# SWD.net
KiCad netlist of a schematic drawn in Altium Designer
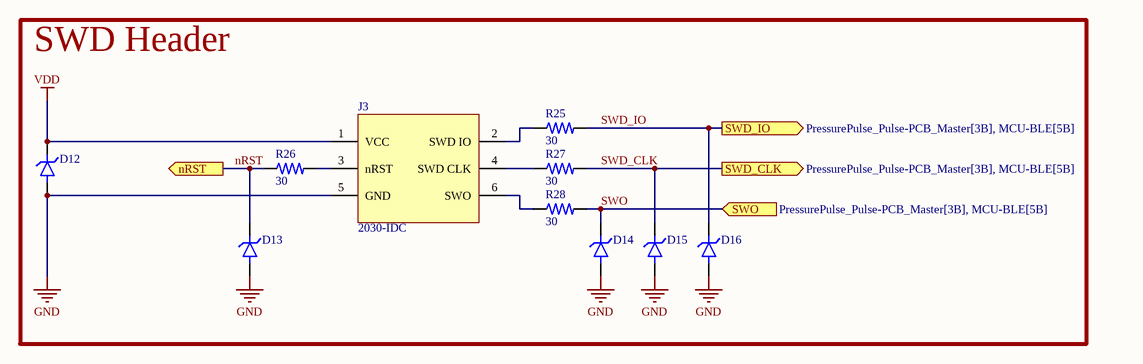
[diagram p0: SWD.SchDoc]

(export (version "E")
  (design (tool "Eeschema 10.0.6"))
  (components
    (comp (ref "D12")
      (value "RCLAMP0521P.TCT")
      (footprint "PressurePulse:BDFN2C051V40")
      (description "25V Clamp 4A (8/20µs) Ipp Tvs Diode Surface Mount SLP1006P2")
      (fields (field (name "MFR") "BORN"))
      (libsource (lib "PressurePulse") (part "TVS DIODE"))
    )
    (comp (ref "D13")
      (value "RCLAMP0521P.TCT")
      (footprint "PressurePulse:BDFN2C051V40")
      (description "25V Clamp 4A (8/20µs) Ipp Tvs Diode Surface Mount SLP1006P2")
      (fields (field (name "MFR") "BORN"))
      (libsource (lib "PressurePulse") (part "TVS DIODE"))
    )
    (comp (ref "D14")
      (value "RCLAMP0521P.TCT")
      (footprint "PressurePulse:BDFN2C051V40")
      (description "25V Clamp 4A (8/20µs) Ipp Tvs Diode Surface Mount SLP1006P2")
      (fields (field (name "MFR") "BORN"))
      (libsource (lib "PressurePulse") (part "TVS DIODE"))
    )
    (comp (ref "D15")
      (value "RCLAMP0521P.TCT")
      (footprint "PressurePulse:BDFN2C051V40")
      (description "25V Clamp 4A (8/20µs) Ipp Tvs Diode Surface Mount SLP1006P2")
      (fields (field (name "MFR") "BORN"))
      (libsource (lib "PressurePulse") (part "TVS DIODE"))
    )
    (comp (ref "D16")
      (value "RCLAMP0521P.TCT")
      (footprint "PressurePulse:BDFN2C051V40")
      (description "25V Clamp 4A (8/20µs) Ipp Tvs Diode Surface Mount SLP1006P2")
      (fields (field (name "MFR") "BORN"))
      (libsource (lib "PressurePulse") (part "TVS DIODE"))
    )
    (comp (ref "J3")
      (value "2030-IDC")
      (footprint "PressurePulse:TAG CONNECT TC2030IDC - NO 3D MODEL")
      (description "TAG CONNECT 2030-IDC")
      (fields (field (name "MFR") "Tag Connect"))
      (libsource (lib "PressurePulse") (part "TAG CONNECT 2030-IDC"))
    )
    (comp (ref "R25")
      (value "30")
      (footprint "PressurePulse:0402R")
      (description "Resistor")
      (fields (field (name "Comment") "RES"))
      (libsource (lib "PressurePulse") (part "RES"))
    )
    (comp (ref "R26")
      (value "30")
      (footprint "PressurePulse:0402R")
      (description "Resistor")
      (fields (field (name "Comment") "RES"))
      (libsource (lib "PressurePulse") (part "RES"))
    )
    (comp (ref "R27")
      (value "30")
      (footprint "PressurePulse:0402R")
      (description "Resistor")
      (fields (field (name "Comment") "RES"))
      (libsource (lib "PressurePulse") (part "RES"))
    )
    (comp (ref "R28")
      (value "30")
      (footprint "PressurePulse:0402R")
      (description "Resistor")
      (fields (field (name "Comment") "RES"))
      (libsource (lib "PressurePulse") (part "RES"))
    )
  )
  (nets
    (net (code "1") (name "/SWD_CLK") (class "Default")
      (node (ref "D15") (pin "K") (pinfunction "K_K") (pintype "passive"))
      (node (ref "R27") (pin "2") (pinfunction "2_2") (pintype "passive"))
    )
    (net (code "2") (name "/SWD_IO") (class "Default")
      (node (ref "D16") (pin "K") (pinfunction "K_K") (pintype "passive"))
      (node (ref "R25") (pin "2") (pinfunction "2_2") (pintype "passive"))
    )
    (net (code "3") (name "/SWO") (class "Default")
      (node (ref "D14") (pin "K") (pinfunction "K_K") (pintype "passive"))
      (node (ref "R28") (pin "2") (pinfunction "2_2") (pintype "passive"))
    )
    (net (code "4") (name "/nRST") (class "Default")
      (node (ref "D13") (pin "K") (pinfunction "K_K") (pintype "passive"))
      (node (ref "R26") (pin "1") (pinfunction "1_1") (pintype "passive"))
    )
    (net (code "5") (name "GND") (class "Default")
      (node (ref "D12") (pin "A") (pinfunction "A_A") (pintype "passive"))
      (node (ref "D13") (pin "A") (pinfunction "A_A") (pintype "passive"))
      (node (ref "D14") (pin "A") (pinfunction "A_A") (pintype "passive"))
      (node (ref "D15") (pin "A") (pinfunction "A_A") (pintype "passive"))
      (node (ref "D16") (pin "A") (pinfunction "A_A") (pintype "passive"))
      (node (ref "J3") (pin "5") (pinfunction "GND_5") (pintype "passive"))
    )
    (net (code "6") (name "Net-(J3-SWD_CLK)") (class "Default")
      (node (ref "J3") (pin "4") (pinfunction "SWD_CLK_4") (pintype "passive"))
      (node (ref "R27") (pin "1") (pinfunction "1_1") (pintype "passive"))
    )
    (net (code "7") (name "Net-(J3-SWD_IO)") (class "Default")
      (node (ref "J3") (pin "2") (pinfunction "SWD_IO_2") (pintype "passive"))
      (node (ref "R25") (pin "1") (pinfunction "1_1") (pintype "passive"))
    )
    (net (code "8") (name "Net-(J3-SWO)") (class "Default")
      (node (ref "J3") (pin "6") (pinfunction "SWO_6") (pintype "passive"))
      (node (ref "R28") (pin "1") (pinfunction "1_1") (pintype "passive"))
    )
    (net (code "9") (name "Net-(J3-nRST)") (class "Default")
      (node (ref "J3") (pin "3") (pinfunction "nRST_3") (pintype "passive"))
      (node (ref "R26") (pin "2") (pinfunction "2_2") (pintype "passive"))
    )
    (net (code "10") (name "VDD") (class "Default")
      (node (ref "D12") (pin "K") (pinfunction "K_K") (pintype "passive"))
      (node (ref "J3") (pin "1") (pinfunction "VCC_1") (pintype "passive"))
    )
  )
)
